# Vezerlo.net
KiCad netlist of a schematic drawn in Altium Designer
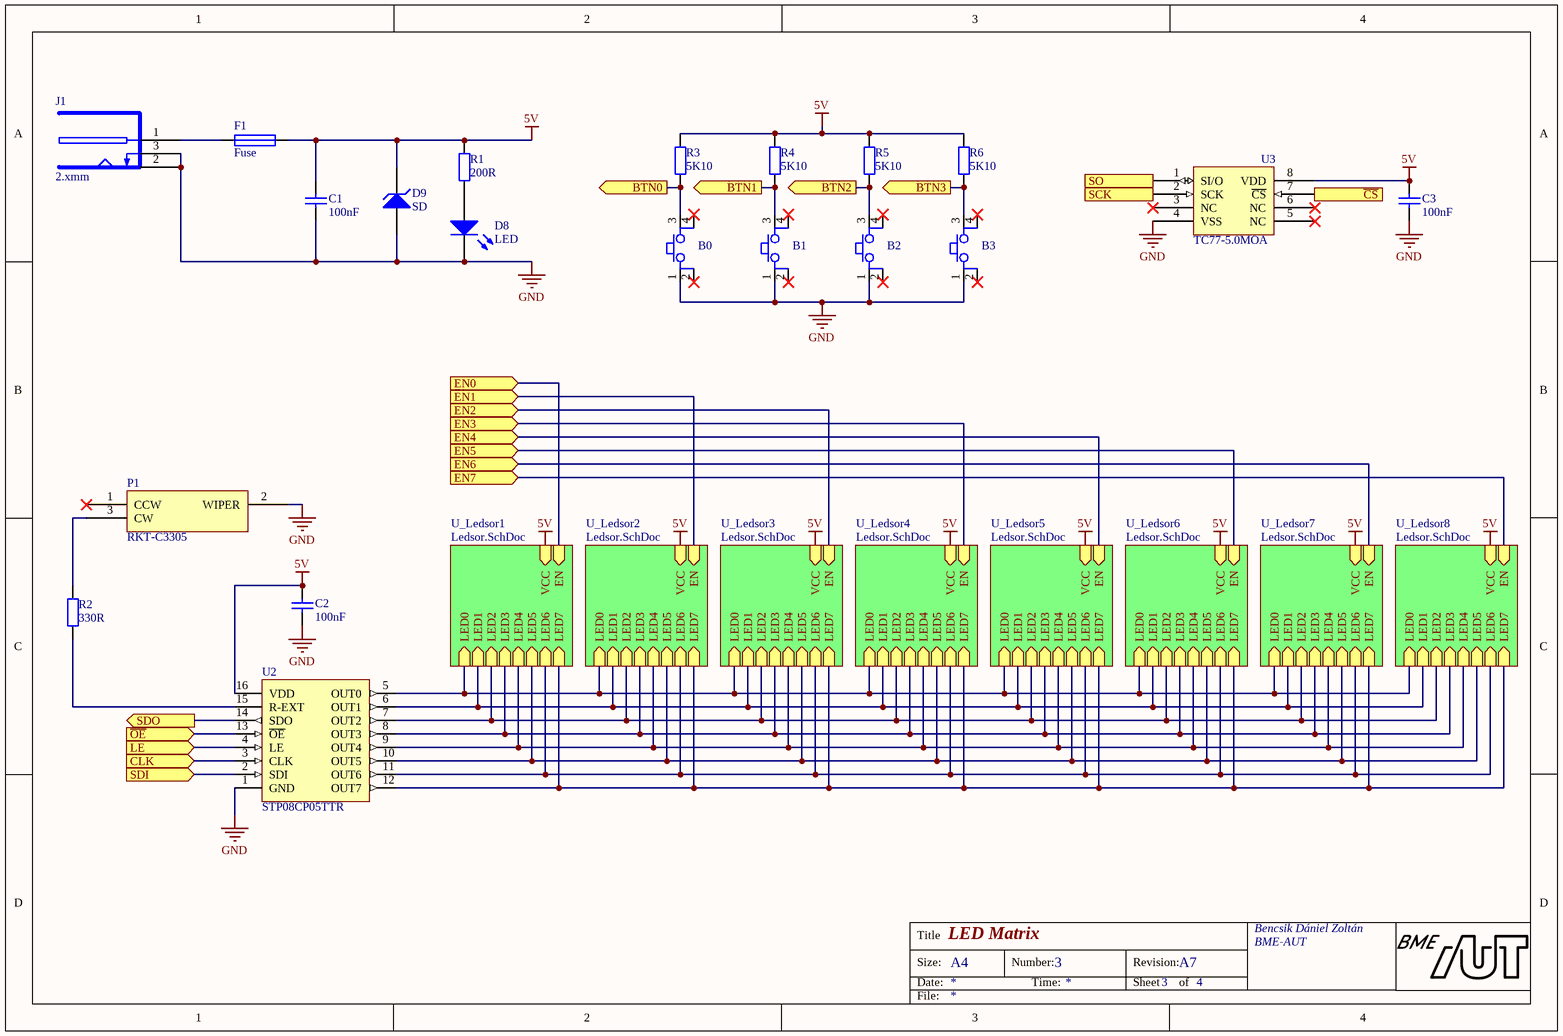
[diagram p0: Vezerlo.SchDoc]

(export (version "E")
  (design (tool "Eeschema 10.0.6"))
  (components
    (comp (ref "B0")
      (value "Button")
      (footprint "FP_BTN_SMD")
      (description "Push button")
      (libsource (lib "hallglib") (part "Button 4P"))
    )
    (comp (ref "B1")
      (value "Button")
      (footprint "FP_BTN_SMD")
      (description "Push button")
      (libsource (lib "hallglib") (part "Button 4P"))
    )
    (comp (ref "B2")
      (value "Button")
      (footprint "FP_BTN_SMD")
      (description "Push button")
      (libsource (lib "hallglib") (part "Button 4P"))
    )
    (comp (ref "B3")
      (value "Button")
      (footprint "FP_BTN_SMD")
      (description "Push button")
      (libsource (lib "hallglib") (part "Button 4P"))
    )
    (comp (ref "C1")
      (value "100nF")
      (footprint "FP_0603_CAP_080")
      (description "Capacitor")
      (libsource (lib "hallglib") (part "CAP"))
    )
    (comp (ref "C2")
      (value "100nF")
      (footprint "FP_0603_CAP_080")
      (description "Capacitor")
      (libsource (lib "hallglib") (part "CAP"))
    )
    (comp (ref "C3")
      (value "100nF")
      (footprint "FP_0603_CAP_080")
      (description "Capacitor")
      (libsource (lib "hallglib") (part "CAP"))
    )
    (comp (ref "D8")
      (value "LED")
      (footprint "HF_FP_0805_LED_BLUE&RED_2")
      (description "Typical RED GaAs LED")
      (libsource (lib "hallglib") (part "LED"))
    )
    (comp (ref "D9")
      (value "SD")
      (footprint "FP_SMA")
      (description "Zener Diode")
      (libsource (lib "hallglib") (part "ZENER"))
    )
    (comp (ref "F1") (value "Fuse") (footprint "FP_MULTIFUSE") (libsource (lib "hallglib") (part "Fuse")))
    (comp (ref "J1")
      (value "2.xmm")
      (footprint "FP_DC_TAP_ANYA")
      (description "2.xmm DC HEBA25 TÁPFESZÜLTSÉG ALJZAT ZÁRT, NYÁKBA 90°")
      (libsource (lib "hallglib") (part "DC_TAP_ANYA"))
    )
    (comp (ref "P1")
      (value "RKT-C3305")
      (footprint "HF_POT")
      (description "TRIMMER POTENTIOMETER-3mm SMD")
      (libsource (lib "hallglib") (part "RKT-C3305"))
    )
    (comp (ref "R1")
      (value "200R")
      (footprint "HF_FP_0603_RES")
      (description "Resistor")
      (libsource (lib "hallglib") (part "RES"))
    )
    (comp (ref "R2")
      (value "330R")
      (footprint "HF_FP_0603_RES")
      (description "Resistor")
      (libsource (lib "hallglib") (part "RES"))
    )
    (comp (ref "R3")
      (value "5K10")
      (footprint "HF_FP_0603_RES")
      (description "Resistor")
      (libsource (lib "hallglib") (part "RES"))
    )
    (comp (ref "R4")
      (value "5K10")
      (footprint "HF_FP_0603_RES")
      (description "Resistor")
      (libsource (lib "hallglib") (part "RES"))
    )
    (comp (ref "R5")
      (value "5K10")
      (footprint "HF_FP_0603_RES")
      (description "Resistor")
      (libsource (lib "hallglib") (part "RES"))
    )
    (comp (ref "R6")
      (value "5K10")
      (footprint "HF_FP_0603_RES")
      (description "Resistor")
      (libsource (lib "hallglib") (part "RES"))
    )
    (comp (ref "U2")
      (value "STP08CP05TTR")
      (footprint "TSOP65P640X120-16M")
      (description "Low voltage, low current power 8-bit shift register")
      (libsource (lib "hallglib") (part "STP08CP05TTR"))
    )
    (comp (ref "U3")
      (value "TC77-5.0MOA")
      (footprint "HF_SOIC127P599X175-8N")
      (description "Thermal Sensor with SPI Interface")
      (libsource (lib "hallglib") (part "TC77-5.0MOA"))
    )
  )
  (nets
    (net (code "1") (name "/BTN0") (class "Default")
      (node (ref "B0") (pin "3") (pinfunction "3_3") (pintype "passive"))
      (node (ref "R3") (pin "1") (pinfunction "1_1") (pintype "passive"))
    )
    (net (code "2") (name "/BTN1") (class "Default")
      (node (ref "B1") (pin "3") (pinfunction "3_3") (pintype "passive"))
      (node (ref "R4") (pin "1") (pinfunction "1_1") (pintype "passive"))
    )
    (net (code "3") (name "/BTN2") (class "Default")
      (node (ref "B2") (pin "3") (pinfunction "3_3") (pintype "passive"))
      (node (ref "R5") (pin "1") (pinfunction "1_1") (pintype "passive"))
    )
    (net (code "4") (name "/BTN3") (class "Default")
      (node (ref "B3") (pin "3") (pinfunction "3_3") (pintype "passive"))
      (node (ref "R6") (pin "1") (pinfunction "1_1") (pintype "passive"))
    )
    (net (code "5") (name "/CLK") (class "Default")
      (node (ref "U2") (pin "3") (pinfunction "CLK_3") (pintype "input"))
    )
    (net (code "14") (name "/LE") (class "Default")
      (node (ref "U2") (pin "4") (pinfunction "LE_4") (pintype "input"))
    )
    (net (code "15") (name "/LED0") (class "Default")
      (node (ref "U2") (pin "5") (pinfunction "OUT0_5") (pintype "output"))
    )
    (net (code "16") (name "/LED1") (class "Default")
      (node (ref "U2") (pin "6") (pinfunction "OUT1_6") (pintype "output"))
    )
    (net (code "17") (name "/LED2") (class "Default")
      (node (ref "U2") (pin "7") (pinfunction "OUT2_7") (pintype "output"))
    )
    (net (code "18") (name "/LED3") (class "Default")
      (node (ref "U2") (pin "8") (pinfunction "OUT3_8") (pintype "output"))
    )
    (net (code "19") (name "/LED4") (class "Default")
      (node (ref "U2") (pin "9") (pinfunction "OUT4_9") (pintype "output"))
    )
    (net (code "20") (name "/LED5") (class "Default")
      (node (ref "U2") (pin "10") (pinfunction "OUT5_10") (pintype "output"))
    )
    (net (code "21") (name "/LED6") (class "Default")
      (node (ref "U2") (pin "11") (pinfunction "OUT6_11") (pintype "output"))
    )
    (net (code "22") (name "/LED7") (class "Default")
      (node (ref "U2") (pin "12") (pinfunction "OUT7_12") (pintype "output"))
    )
    (net (code "23") (name "/SCK") (class "Default")
      (node (ref "U3") (pin "2") (pinfunction "SCK_2") (pintype "input"))
    )
    (net (code "24") (name "/SDI") (class "Default")
      (node (ref "U2") (pin "2") (pinfunction "SDI_2") (pintype "input"))
    )
    (net (code "25") (name "/SDO") (class "Default")
      (node (ref "U2") (pin "14") (pinfunction "SDO_14") (pintype "output"))
    )
    (net (code "26") (name "/SO") (class "Default")
      (node (ref "U3") (pin "1") (pinfunction "SI/O_1") (pintype "bidirectional"))
    )
    (net (code "27") (name "/~{CS}") (class "Default")
      (node (ref "U3") (pin "7") (pinfunction "~{CS}_7") (pintype "input"))
    )
    (net (code "28") (name "/~{OE}") (class "Default")
      (node (ref "U2") (pin "13") (pinfunction "~{OE}_13") (pintype "input"))
    )
    (net (code "29") (name "5V") (class "Default")
      (node (ref "C1") (pin "2") (pinfunction "2_2") (pintype "passive"))
      (node (ref "C2") (pin "2") (pinfunction "2_2") (pintype "passive"))
      (node (ref "C3") (pin "2") (pinfunction "2_2") (pintype "passive"))
      (node (ref "D9") (pin "K") (pinfunction "2_K") (pintype "passive"))
      (node (ref "F1") (pin "2") (pinfunction "2_2") (pintype "passive"))
      (node (ref "R1") (pin "2") (pinfunction "2_2") (pintype "passive"))
      (node (ref "R3") (pin "2") (pinfunction "2_2") (pintype "passive"))
      (node (ref "R4") (pin "2") (pinfunction "2_2") (pintype "passive"))
      (node (ref "R5") (pin "2") (pinfunction "2_2") (pintype "passive"))
      (node (ref "R6") (pin "2") (pinfunction "2_2") (pintype "passive"))
      (node (ref "U2") (pin "16") (pinfunction "VDD_16") (pintype "power_in"))
      (node (ref "U3") (pin "8") (pinfunction "VDD_8") (pintype "power_in"))
    )
    (net (code "30") (name "GND") (class "Default")
      (node (ref "B0") (pin "1") (pinfunction "1_1") (pintype "passive"))
      (node (ref "B1") (pin "1") (pinfunction "1_1") (pintype "passive"))
      (node (ref "B2") (pin "1") (pinfunction "1_1") (pintype "passive"))
      (node (ref "B3") (pin "1") (pinfunction "1_1") (pintype "passive"))
      (node (ref "C1") (pin "1") (pinfunction "1_1") (pintype "passive"))
      (node (ref "C2") (pin "1") (pinfunction "1_1") (pintype "passive"))
      (node (ref "C3") (pin "1") (pinfunction "1_1") (pintype "passive"))
      (node (ref "D8") (pin "K") (pinfunction "2_K") (pintype "passive"))
      (node (ref "D9") (pin "A") (pinfunction "1_A") (pintype "passive"))
      (node (ref "J1") (pin "2") (pinfunction "SLEEVE_2") (pintype "power_in"))
      (node (ref "J1") (pin "3") (pinfunction "BREAK_3") (pintype "power_in"))
      (node (ref "P1") (pin "2") (pinfunction "WIPER_2") (pintype "passive"))
      (node (ref "U2") (pin "1") (pinfunction "GND_1") (pintype "passive"))
      (node (ref "U3") (pin "4") (pinfunction "VSS_4") (pintype "power_in"))
    )
    (net (code "31") (name "Net-(D8-1)") (class "Default")
      (node (ref "D8") (pin "A") (pinfunction "1_A") (pintype "passive"))
      (node (ref "R1") (pin "1") (pinfunction "1_1") (pintype "passive"))
    )
    (net (code "32") (name "Net-(J1-PIN)") (class "Default")
      (node (ref "F1") (pin "1") (pinfunction "1_1") (pintype "passive"))
      (node (ref "J1") (pin "1") (pinfunction "PIN_1") (pintype "power_in"))
    )
    (net (code "33") (name "Net-(P1-CW)") (class "Default")
      (node (ref "P1") (pin "3") (pinfunction "CW_3") (pintype "passive"))
      (node (ref "R2") (pin "2") (pinfunction "2_2") (pintype "passive"))
    )
    (net (code "34") (name "Net-(U2-R-EXT)") (class "Default")
      (node (ref "R2") (pin "1") (pinfunction "1_1") (pintype "passive"))
      (node (ref "U2") (pin "15") (pinfunction "R-EXT_15") (pintype "passive"))
    )
    (net (code "35") (name "unconnected-(B0-Pad2)") (class "Default")
      (node (ref "B0") (pin "2") (pinfunction "2_2") (pintype "passive+no_connect"))
    )
    (net (code "36") (name "unconnected-(B0-Pad4)") (class "Default")
      (node (ref "B0") (pin "4") (pinfunction "4_4") (pintype "passive+no_connect"))
    )
    (net (code "37") (name "unconnected-(B1-Pad2)") (class "Default")
      (node (ref "B1") (pin "2") (pinfunction "2_2") (pintype "passive+no_connect"))
    )
    (net (code "38") (name "unconnected-(B1-Pad4)") (class "Default")
      (node (ref "B1") (pin "4") (pinfunction "4_4") (pintype "passive+no_connect"))
    )
    (net (code "39") (name "unconnected-(B2-Pad2)") (class "Default")
      (node (ref "B2") (pin "2") (pinfunction "2_2") (pintype "passive+no_connect"))
    )
    (net (code "40") (name "unconnected-(B2-Pad4)") (class "Default")
      (node (ref "B2") (pin "4") (pinfunction "4_4") (pintype "passive+no_connect"))
    )
    (net (code "41") (name "unconnected-(B3-Pad2)") (class "Default")
      (node (ref "B3") (pin "2") (pinfunction "2_2") (pintype "passive+no_connect"))
    )
    (net (code "42") (name "unconnected-(B3-Pad4)") (class "Default")
      (node (ref "B3") (pin "4") (pinfunction "4_4") (pintype "passive+no_connect"))
    )
    (net (code "43") (name "unconnected-(P1-CCW-Pad1)") (class "Default")
      (node (ref "P1") (pin "1") (pinfunction "CCW_1") (pintype "passive+no_connect"))
    )
    (net (code "44") (name "unconnected-(U3-NC-Pad3)") (class "Default")
      (node (ref "U3") (pin "3") (pinfunction "NC_3") (pintype "passive+no_connect"))
    )
    (net (code "45") (name "unconnected-(U3-NC-Pad5)") (class "Default")
      (node (ref "U3") (pin "5") (pinfunction "NC_5") (pintype "passive+no_connect"))
    )
    (net (code "46") (name "unconnected-(U3-NC-Pad6)") (class "Default")
      (node (ref "U3") (pin "6") (pinfunction "NC_6") (pintype "passive+no_connect"))
    )
  )
)
